# ring-modulator.net
KiCad netlist of a schematic drawn in EAGLE
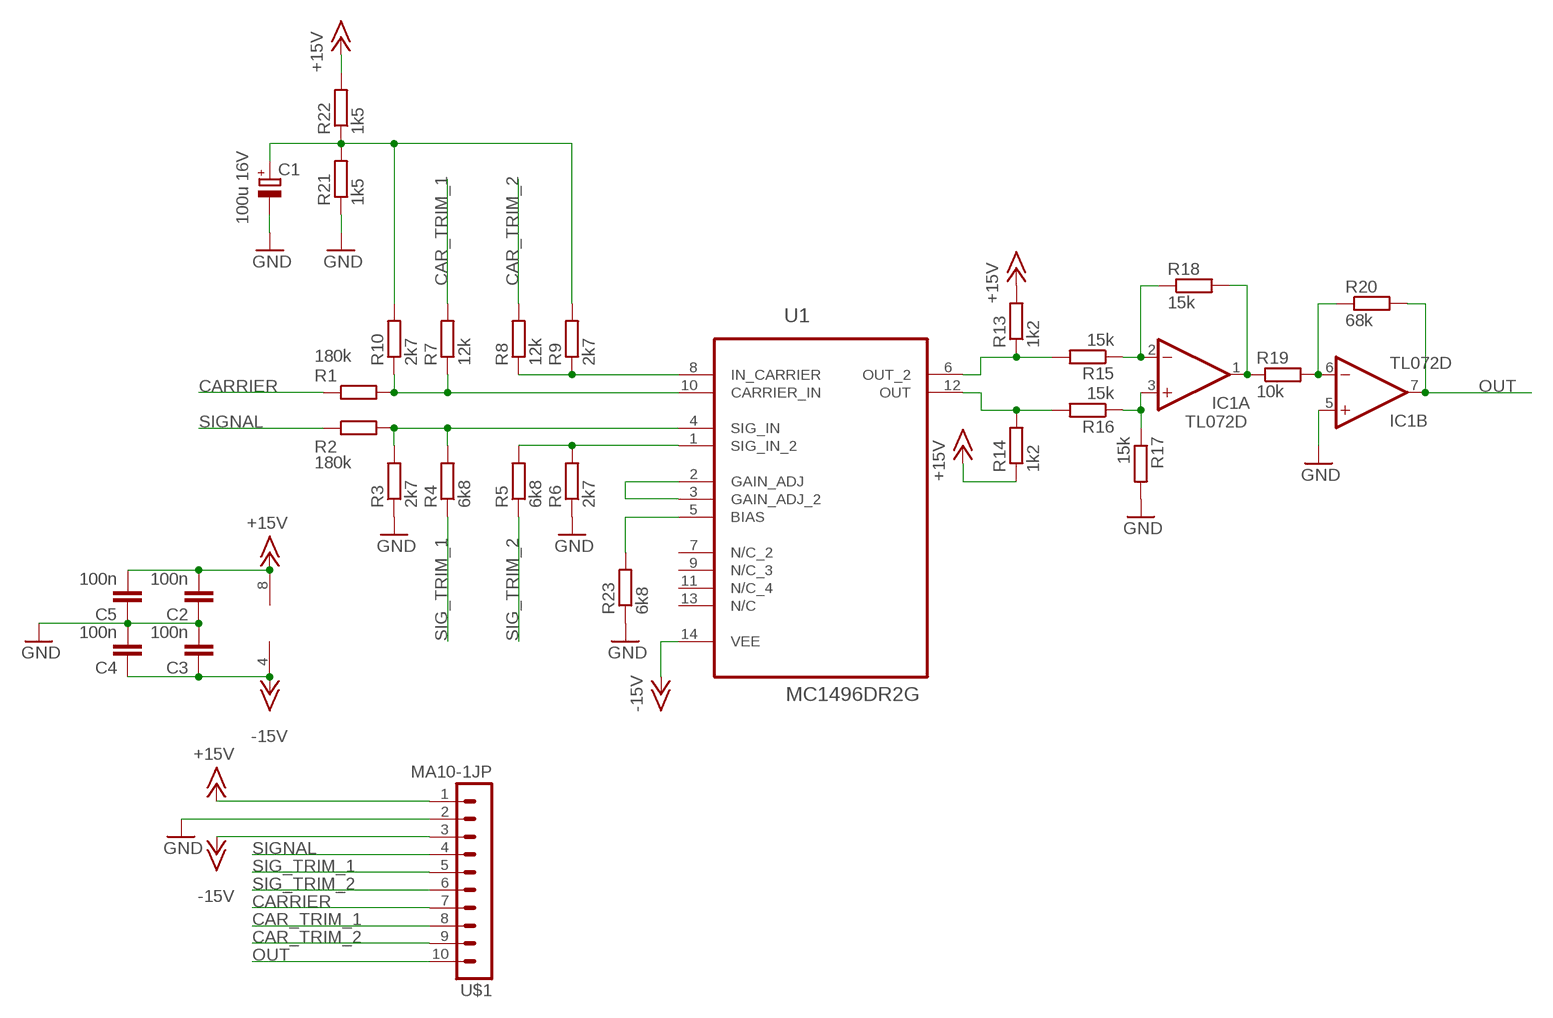
[diagram p0: schematic, sheet 1]

(export (version "E")
  (design (tool "Eeschema 10.0.6"))
  (components
    (comp (ref "C1")
      (value "100u 16V")
      (footprint "eagle-import:E2,5-5")
      (libsource (lib "eagle-import") (part "CPOL-EUE2.5-5"))
    )
    (comp (ref "C2")
      (value "100n")
      (footprint "eagle-import:C0805")
      (libsource (lib "eagle-import") (part "C-EUC0805"))
    )
    (comp (ref "C3")
      (value "100n")
      (footprint "eagle-import:C0805")
      (libsource (lib "eagle-import") (part "C-EUC0805"))
    )
    (comp (ref "C4")
      (value "100n")
      (footprint "eagle-import:C0805")
      (libsource (lib "eagle-import") (part "C-EUC0805"))
    )
    (comp (ref "C5")
      (value "100n")
      (footprint "eagle-import:C0805")
      (libsource (lib "eagle-import") (part "C-EUC0805"))
    )
    (comp (ref "IC1")
      (value "TL072D")
      (footprint "eagle-import:SO08J")
      (libsource (lib "eagle-import") (part "TL072D"))
    )
    (comp (ref "R1")
      (value "180k")
      (footprint "eagle-import:R0805")
      (libsource (lib "eagle-import") (part "R-EU_R0805"))
    )
    (comp (ref "R2")
      (value "180k")
      (footprint "eagle-import:R0805")
      (libsource (lib "eagle-import") (part "R-EU_R0805"))
    )
    (comp (ref "R3")
      (value "2k7")
      (footprint "eagle-import:R0805")
      (libsource (lib "eagle-import") (part "R-EU_R0805"))
    )
    (comp (ref "R4")
      (value "6k8")
      (footprint "eagle-import:R0805")
      (libsource (lib "eagle-import") (part "R-EU_R0805"))
    )
    (comp (ref "R5")
      (value "6k8")
      (footprint "eagle-import:R0805")
      (libsource (lib "eagle-import") (part "R-EU_R0805"))
    )
    (comp (ref "R6")
      (value "2k7")
      (footprint "eagle-import:R0805")
      (libsource (lib "eagle-import") (part "R-EU_R0805"))
    )
    (comp (ref "R7")
      (value "12k")
      (footprint "eagle-import:R0805")
      (libsource (lib "eagle-import") (part "R-EU_R0805"))
    )
    (comp (ref "R8")
      (value "12k")
      (footprint "eagle-import:R0805")
      (libsource (lib "eagle-import") (part "R-EU_R0805"))
    )
    (comp (ref "R9")
      (value "2k7")
      (footprint "eagle-import:R0805")
      (libsource (lib "eagle-import") (part "R-EU_R0805"))
    )
    (comp (ref "R10")
      (value "2k7")
      (footprint "eagle-import:R0805")
      (libsource (lib "eagle-import") (part "R-EU_R0805"))
    )
    (comp (ref "R13")
      (value "1k2")
      (footprint "eagle-import:R0805")
      (libsource (lib "eagle-import") (part "R-EU_R0805"))
    )
    (comp (ref "R14")
      (value "1k2")
      (footprint "eagle-import:R0805")
      (libsource (lib "eagle-import") (part "R-EU_R0805"))
    )
    (comp (ref "R15")
      (value "15k")
      (footprint "eagle-import:R0805")
      (libsource (lib "eagle-import") (part "R-EU_R0805"))
    )
    (comp (ref "R16")
      (value "15k")
      (footprint "eagle-import:R0805")
      (libsource (lib "eagle-import") (part "R-EU_R0805"))
    )
    (comp (ref "R17")
      (value "15k")
      (footprint "eagle-import:R0805")
      (libsource (lib "eagle-import") (part "R-EU_R0805"))
    )
    (comp (ref "R18")
      (value "15k")
      (footprint "eagle-import:R0805")
      (libsource (lib "eagle-import") (part "R-EU_R0805"))
    )
    (comp (ref "R19")
      (value "10k")
      (footprint "eagle-import:R0805")
      (libsource (lib "eagle-import") (part "R-EU_R0805"))
    )
    (comp (ref "R20")
      (value "68k")
      (footprint "eagle-import:R0805")
      (libsource (lib "eagle-import") (part "R-EU_R0805"))
    )
    (comp (ref "R21")
      (value "1k5")
      (footprint "eagle-import:R0805")
      (libsource (lib "eagle-import") (part "R-EU_R0805"))
    )
    (comp (ref "R22")
      (value "1k5")
      (footprint "eagle-import:R0805")
      (libsource (lib "eagle-import") (part "R-EU_R0805"))
    )
    (comp (ref "R23")
      (value "6k8")
      (footprint "eagle-import:R0805")
      (libsource (lib "eagle-import") (part "R-EU_R0805"))
    )
    (comp (ref "U$1")
      (value "MA10-1JP")
      (footprint "eagle-import:SIP-PIN10-1J")
      (libsource (lib "eagle-import") (part "MA10-1JP"))
    )
    (comp (ref "U1")
      (value "MC1496DR2G")
      (footprint "eagle-import:SOIC127P600X175-14N")
      (libsource (lib "eagle-import") (part "MC1496DR2G"))
    )
  )
  (nets
    (net (code "1") (name "+15V") (class "Default")
      (node (ref "C2") (pin "2") (pinfunction "2_2") (pintype "passive"))
      (node (ref "C5") (pin "2") (pinfunction "2_2") (pintype "passive"))
      (node (ref "IC1") (pin "8") (pinfunction "V+_8") (pintype "power_in"))
      (node (ref "R13") (pin "2") (pinfunction "2_2") (pintype "passive"))
      (node (ref "R14") (pin "1") (pinfunction "1_1") (pintype "passive"))
      (node (ref "R22") (pin "2") (pinfunction "2_2") (pintype "passive"))
      (node (ref "U$1") (pin "1") (pinfunction "1_1") (pintype "passive"))
    )
    (net (code "2") (name "-15V") (class "Default")
      (node (ref "C3") (pin "1") (pinfunction "1_1") (pintype "passive"))
      (node (ref "C4") (pin "1") (pinfunction "1_1") (pintype "passive"))
      (node (ref "IC1") (pin "4") (pinfunction "V-_4") (pintype "power_in"))
      (node (ref "U$1") (pin "3") (pinfunction "3_3") (pintype "passive"))
      (node (ref "U1") (pin "14") (pinfunction "VEE_14") (pintype "passive"))
    )
    (net (code "3") (name "/CARRIER") (class "Default")
      (node (ref "R1") (pin "1") (pinfunction "1_1") (pintype "passive"))
      (node (ref "U$1") (pin "7") (pinfunction "7_7") (pintype "passive"))
    )
    (net (code "4") (name "/CAR_TRIM_1") (class "Default")
      (node (ref "R7") (pin "2") (pinfunction "2_2") (pintype "passive"))
      (node (ref "U$1") (pin "8") (pinfunction "8_8") (pintype "passive"))
    )
    (net (code "5") (name "/CAR_TRIM_2") (class "Default")
      (node (ref "R8") (pin "2") (pinfunction "2_2") (pintype "passive"))
      (node (ref "U$1") (pin "9") (pinfunction "9_9") (pintype "passive"))
    )
    (net (code "6") (name "/OUT") (class "Default")
      (node (ref "IC1") (pin "7") (pinfunction "OUT_7") (pintype "output"))
      (node (ref "R20") (pin "2") (pinfunction "2_2") (pintype "passive"))
      (node (ref "U$1") (pin "10") (pinfunction "10_10") (pintype "passive"))
    )
    (net (code "7") (name "/SIGNAL") (class "Default")
      (node (ref "R2") (pin "1") (pinfunction "1_1") (pintype "passive"))
      (node (ref "U$1") (pin "4") (pinfunction "4_4") (pintype "passive"))
    )
    (net (code "8") (name "/SIG_TRIM_1") (class "Default")
      (node (ref "R4") (pin "1") (pinfunction "1_1") (pintype "passive"))
      (node (ref "U$1") (pin "5") (pinfunction "5_5") (pintype "passive"))
    )
    (net (code "9") (name "/SIG_TRIM_2") (class "Default")
      (node (ref "R5") (pin "1") (pinfunction "1_1") (pintype "passive"))
      (node (ref "U$1") (pin "6") (pinfunction "6_6") (pintype "passive"))
    )
    (net (code "10") (name "GND") (class "Default")
      (node (ref "C1") (pin "-") (pinfunction "-_-") (pintype "passive"))
      (node (ref "C2") (pin "1") (pinfunction "1_1") (pintype "passive"))
      (node (ref "C3") (pin "2") (pinfunction "2_2") (pintype "passive"))
      (node (ref "C4") (pin "2") (pinfunction "2_2") (pintype "passive"))
      (node (ref "C5") (pin "1") (pinfunction "1_1") (pintype "passive"))
      (node (ref "IC1") (pin "5") (pinfunction "+IN_5") (pintype "input"))
      (node (ref "R17") (pin "2") (pinfunction "2_2") (pintype "passive"))
      (node (ref "R21") (pin "1") (pinfunction "1_1") (pintype "passive"))
      (node (ref "R23") (pin "1") (pinfunction "1_1") (pintype "passive"))
      (node (ref "R3") (pin "1") (pinfunction "1_1") (pintype "passive"))
      (node (ref "R6") (pin "1") (pinfunction "1_1") (pintype "passive"))
      (node (ref "U$1") (pin "2") (pinfunction "2_2") (pintype "passive"))
    )
    (net (code "11") (name "Net-(C1-Pad+)") (class "Default")
      (node (ref "C1") (pin "+") (pinfunction "+_+") (pintype "passive"))
      (node (ref "R10") (pin "2") (pinfunction "2_2") (pintype "passive"))
      (node (ref "R21") (pin "2") (pinfunction "2_2") (pintype "passive"))
      (node (ref "R22") (pin "1") (pinfunction "1_1") (pintype "passive"))
      (node (ref "R9") (pin "2") (pinfunction "2_2") (pintype "passive"))
    )
    (net (code "12") (name "Net-(IC1A-+IN)") (class "Default")
      (node (ref "IC1") (pin "3") (pinfunction "+IN_3") (pintype "input"))
      (node (ref "R16") (pin "1") (pinfunction "1_1") (pintype "passive"))
      (node (ref "R17") (pin "1") (pinfunction "1_1") (pintype "passive"))
    )
    (net (code "13") (name "Net-(IC1A--IN)") (class "Default")
      (node (ref "IC1") (pin "2") (pinfunction "-IN_2") (pintype "input"))
      (node (ref "R15") (pin "1") (pinfunction "1_1") (pintype "passive"))
      (node (ref "R18") (pin "1") (pinfunction "1_1") (pintype "passive"))
    )
    (net (code "14") (name "Net-(IC1A-OUT)") (class "Default")
      (node (ref "IC1") (pin "1") (pinfunction "OUT_1") (pintype "output"))
      (node (ref "R18") (pin "2") (pinfunction "2_2") (pintype "passive"))
      (node (ref "R19") (pin "1") (pinfunction "1_1") (pintype "passive"))
    )
    (net (code "15") (name "Net-(IC1B--IN)") (class "Default")
      (node (ref "IC1") (pin "6") (pinfunction "-IN_6") (pintype "input"))
      (node (ref "R19") (pin "2") (pinfunction "2_2") (pintype "passive"))
      (node (ref "R20") (pin "1") (pinfunction "1_1") (pintype "passive"))
    )
    (net (code "16") (name "Net-(U1-BIAS)") (class "Default")
      (node (ref "R23") (pin "2") (pinfunction "2_2") (pintype "passive"))
      (node (ref "U1") (pin "5") (pinfunction "BIAS_5") (pintype "input"))
    )
    (net (code "17") (name "Net-(U1-CARRIER_IN)") (class "Default")
      (node (ref "R1") (pin "2") (pinfunction "2_2") (pintype "passive"))
      (node (ref "R10") (pin "1") (pinfunction "1_1") (pintype "passive"))
      (node (ref "R7") (pin "1") (pinfunction "1_1") (pintype "passive"))
      (node (ref "U1") (pin "10") (pinfunction "CARRIER_IN_10") (pintype "power_in"))
    )
    (net (code "18") (name "Net-(U1-GAIN_ADJ)") (class "Default")
      (node (ref "U1") (pin "2") (pinfunction "GAIN_ADJ_2") (pintype "input"))
      (node (ref "U1") (pin "3") (pinfunction "GAIN_ADJ_2_3") (pintype "input"))
    )
    (net (code "19") (name "Net-(U1-IN_CARRIER)") (class "Default")
      (node (ref "R8") (pin "1") (pinfunction "1_1") (pintype "passive"))
      (node (ref "R9") (pin "1") (pinfunction "1_1") (pintype "passive"))
      (node (ref "U1") (pin "8") (pinfunction "IN_CARRIER_8") (pintype "power_in"))
    )
    (net (code "20") (name "Net-(U1-OUT)") (class "Default")
      (node (ref "R14") (pin "2") (pinfunction "2_2") (pintype "passive"))
      (node (ref "R16") (pin "2") (pinfunction "2_2") (pintype "passive"))
      (node (ref "U1") (pin "12") (pinfunction "OUT_12") (pintype "output"))
    )
    (net (code "21") (name "Net-(U1-OUT_2)") (class "Default")
      (node (ref "R13") (pin "1") (pinfunction "1_1") (pintype "passive"))
      (node (ref "R15") (pin "2") (pinfunction "2_2") (pintype "passive"))
      (node (ref "U1") (pin "6") (pinfunction "OUT_2_6") (pintype "output"))
    )
    (net (code "22") (name "Net-(U1-SIG_IN)") (class "Default")
      (node (ref "R2") (pin "2") (pinfunction "2_2") (pintype "passive"))
      (node (ref "R3") (pin "2") (pinfunction "2_2") (pintype "passive"))
      (node (ref "R4") (pin "2") (pinfunction "2_2") (pintype "passive"))
      (node (ref "U1") (pin "4") (pinfunction "SIG_IN_4") (pintype "input"))
    )
    (net (code "23") (name "Net-(U1-SIG_IN_2)") (class "Default")
      (node (ref "R5") (pin "2") (pinfunction "2_2") (pintype "passive"))
      (node (ref "R6") (pin "2") (pinfunction "2_2") (pintype "passive"))
      (node (ref "U1") (pin "1") (pinfunction "SIG_IN_2_1") (pintype "input"))
    )
    (net (code "24") (name "unconnected-(U1-N{slash}C-Pad13)") (class "Default")
      (node (ref "U1") (pin "13") (pinfunction "N/C_13") (pintype "no_connect"))
    )
    (net (code "25") (name "unconnected-(U1-N{slash}C_2-Pad7)") (class "Default")
      (node (ref "U1") (pin "7") (pinfunction "N/C_2_7") (pintype "no_connect"))
    )
    (net (code "26") (name "unconnected-(U1-N{slash}C_3-Pad9)") (class "Default")
      (node (ref "U1") (pin "9") (pinfunction "N/C_3_9") (pintype "no_connect"))
    )
    (net (code "27") (name "unconnected-(U1-N{slash}C_4-Pad11)") (class "Default")
      (node (ref "U1") (pin "11") (pinfunction "N/C_4_11") (pintype "no_connect"))
    )
  )
)
